# PROC051D_XDS110_Interface_1B.net
KiCad netlist of a schematic drawn in Altium Designer
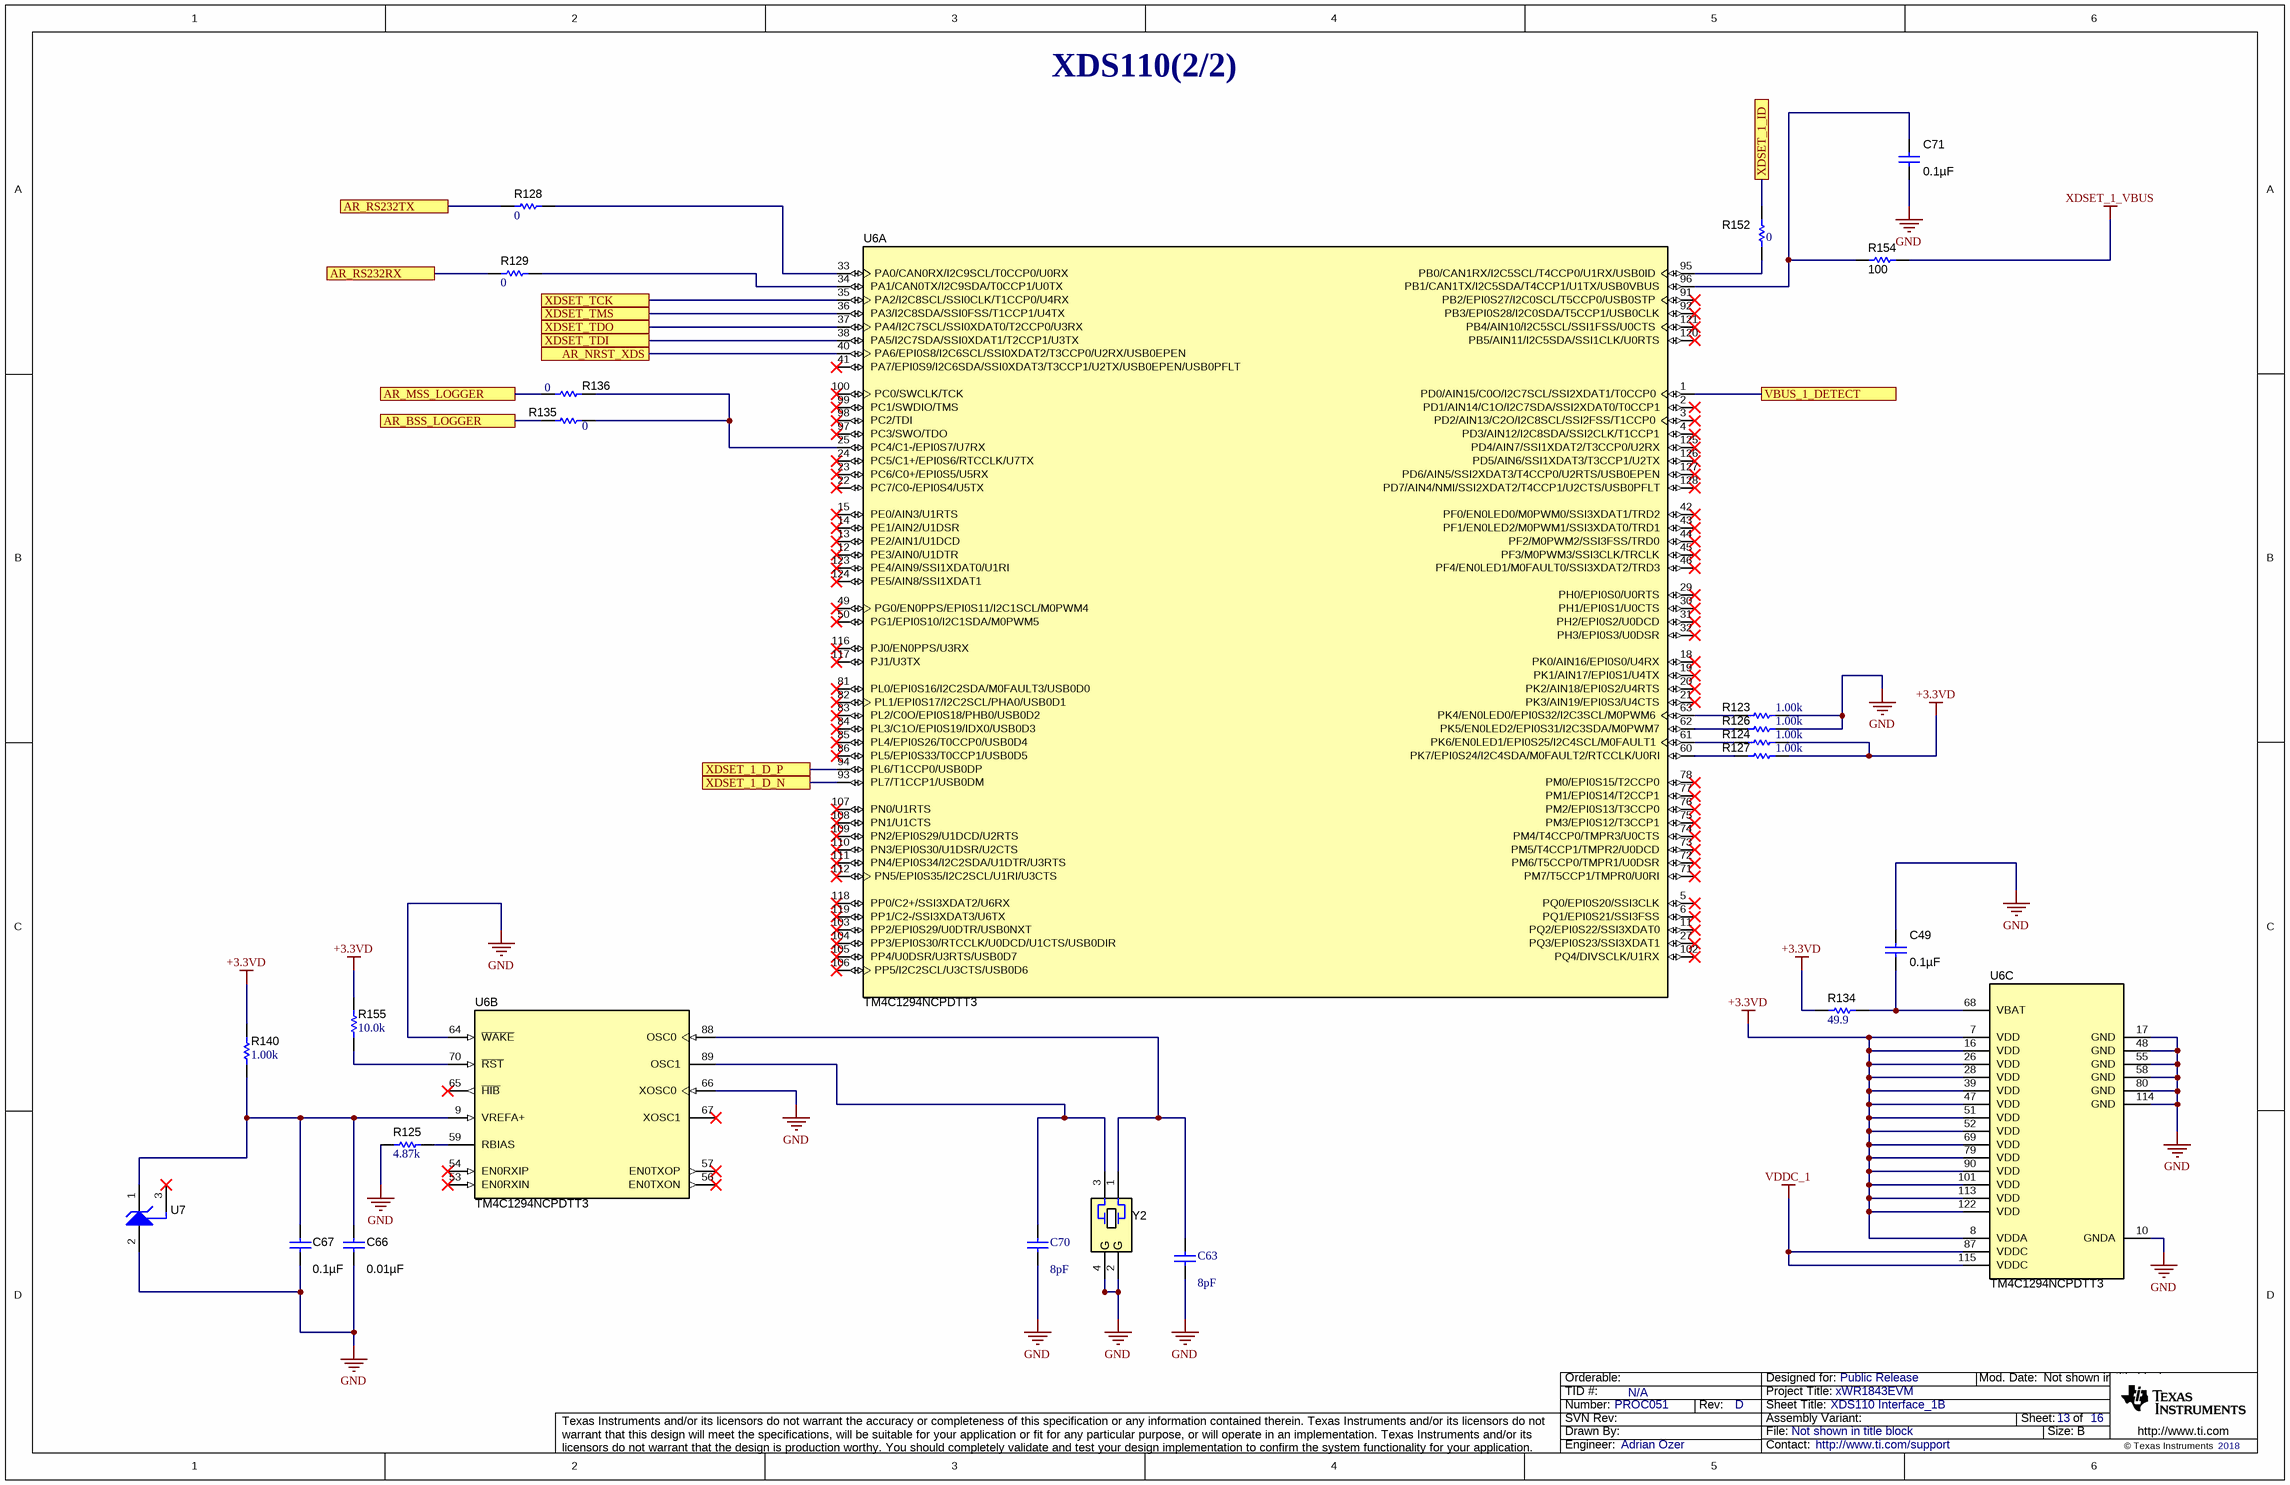
[diagram p0: PROC051D_XDS110 Interface_1B.SchDoc]

(export (version "E")
  (design (tool "Eeschema 10.0.6"))
  (components
    (comp (ref "C49")
      (value "C0402C104K8RACTU")
      (footprint "0402L")
      (description "CAP, CERM, 0.1 µF, 10 V,+/- 10%, X7R, 0402")
      (fields (field (name "MANUFACTURER") "Kemet") (field (name "VALUEDISPLAYED") "0.1µF"))
      (libsource (lib "Altium Vault - TI") (part "CMP-0078241-1"))
    )
    (comp (ref "C63")
      (value "GCM1555C1H8R0DA16D")
      (footprint "0402L")
      (description "Cap Ceramic 8pF 50V C0G 0.5pF SMD 0402 125C Paper T/R")
      (fields (field (name "CAP_F") "8pF") (field (name "MANUFACTURER") "Murata Electronics North America"))
      (libsource (lib "Altium Vault - TI") (part "CMP-0087060-3"))
    )
    (comp (ref "C66")
      (value "C0402C103K4RACTU")
      (footprint "0402L")
      (description "CAP, CERM, 0.01 µF, 16 V,+/- 10%, X7R, 0402")
      (fields (field (name "MANUFACTURER") "Kemet") (field (name "VALUEDISPLAYED") "0.01µF"))
      (libsource (lib "Altium Vault - TI") (part "Capacitor"))
    )
    (comp (ref "C67")
      (value "C0402C104K8RACTU")
      (footprint "0402L")
      (description "CAP, CERM, 0.1 µF, 10 V,+/- 10%, X7R, 0402")
      (fields (field (name "MANUFACTURER") "Kemet") (field (name "VALUEDISPLAYED") "0.1µF"))
      (libsource (lib "Altium Vault - TI") (part "Capacitor"))
    )
    (comp (ref "C70")
      (value "GCM1555C1H8R0DA16D")
      (footprint "0402L")
      (description "Cap Ceramic 8pF 50V C0G 0.5pF SMD 0402 125C Paper T/R")
      (fields (field (name "CAP_F") "8pF") (field (name "MANUFACTURER") "Murata Electronics North America"))
      (libsource (lib "Altium Vault - TI") (part "CMP-0087060-3"))
    )
    (comp (ref "C71")
      (value "C0402C104K8RACTU")
      (footprint "0402L")
      (description "CAP, CERM, 0.1 µF, 10 V,+/- 10%, X7R, 0402")
      (fields (field (name "MANUFACTURER") "Kemet") (field (name "VALUEDISPLAYED") "0.1µF"))
      (libsource (lib "Altium Vault - TI") (part "Capacitor"))
    )
    (comp (ref "R123")
      (value "CRCW04021K00FKED")
      (footprint "0402L")
      (description "RES, 1.00 k, 1%, 0.063 W, AEC-Q200 Grade 0, 0402")
      (fields (field (name "MANUFACTURER") "Vishay-Dale") (field (name "VALUEDISPLAYED") "1.00k"))
      (libsource (lib "Altium Vault - TI") (part "Resistor"))
    )
    (comp (ref "R124")
      (value "CRCW04021K00FKED")
      (footprint "0402L")
      (description "RES, 1.00 k, 1%, 0.063 W, AEC-Q200 Grade 0, 0402")
      (fields (field (name "MANUFACTURER") "Vishay-Dale") (field (name "VALUEDISPLAYED") "1.00k"))
      (libsource (lib "Altium Vault - TI") (part "Resistor"))
    )
    (comp (ref "R125")
      (value "CRCW04024K87FKED")
      (footprint "0402L")
      (description "RES, 4.87 k, 1%, 0.063 W, AEC-Q200 Grade 0, 0402")
      (fields (field (name "MANUFACTURER") "Vishay-Dale") (field (name "VALUEDISPLAYED") "4.87k"))
      (libsource (lib "Altium Vault - TI") (part "Resistor"))
    )
    (comp (ref "R126")
      (value "CRCW04021K00FKED")
      (footprint "0402L")
      (description "RES, 1.00 k, 1%, 0.063 W, AEC-Q200 Grade 0, 0402")
      (fields (field (name "MANUFACTURER") "Vishay-Dale") (field (name "VALUEDISPLAYED") "1.00k"))
      (libsource (lib "Altium Vault - TI") (part "Resistor"))
    )
    (comp (ref "R127")
      (value "CRCW04021K00FKED")
      (footprint "0402L")
      (description "RES, 1.00 k, 1%, 0.063 W, AEC-Q200 Grade 0, 0402")
      (fields (field (name "MANUFACTURER") "Vishay-Dale") (field (name "VALUEDISPLAYED") "1.00k"))
      (libsource (lib "Altium Vault - TI") (part "Resistor"))
    )
    (comp (ref "R128")
      (value "ERJ-2GE0R00X")
      (footprint "0402L")
      (description "RES, 0, 5%, 0.1 W, AEC-Q200 Grade 0, 0402")
      (fields (field (name "MANUFACTURER") "Panasonic") (field (name "VALUEDISPLAYED") "0"))
      (libsource (lib "Altium Vault - TI") (part "Resistor"))
    )
    (comp (ref "R129")
      (value "ERJ-2GE0R00X")
      (footprint "0402L")
      (description "RES, 0, 5%, 0.1 W, AEC-Q200 Grade 0, 0402")
      (fields (field (name "MANUFACTURER") "Panasonic") (field (name "VALUEDISPLAYED") "0"))
      (libsource (lib "Altium Vault - TI") (part "Resistor"))
    )
    (comp (ref "R134")
      (value "CRCW040249R9FKED")
      (footprint "0402L")
      (description "RES, 49.9, 1%, 0.063 W, AEC-Q200 Grade 0, 0402")
      (fields (field (name "MANUFACTURER") "Vishay-Dale") (field (name "VALUEDISPLAYED") "49.9"))
      (libsource (lib "Altium Vault - TI") (part "Resistor"))
    )
    (comp (ref "R135")
      (value "CRCW02010000Z0ED")
      (footprint "0201_Silk")
      (description "RES, 0, 5%, 0.05 W, 0201")
      (fields (field (name "MANUFACTURER") "Vishay-Dale") (field (name "VALUEDISPLAYED") "0"))
      (libsource (lib "Altium Vault - TI") (part "Resistor"))
    )
    (comp (ref "R136")
      (value "CRCW02010000Z0ED")
      (footprint "0201_Silk")
      (description "RES, 0, 5%, 0.05 W, 0201")
      (fields (field (name "MANUFACTURER") "Vishay-Dale") (field (name "VALUEDISPLAYED") "0"))
      (libsource (lib "Altium Vault - TI") (part "Resistor"))
    )
    (comp (ref "R140")
      (value "CRCW04021K00FKED")
      (footprint "0402L")
      (description "RES, 1.00 k, 1%, 0.063 W, AEC-Q200 Grade 0, 0402")
      (fields (field (name "MANUFACTURER") "Vishay-Dale") (field (name "VALUEDISPLAYED") "1.00k"))
      (libsource (lib "Altium Vault - TI") (part "Resistor"))
    )
    (comp (ref "R152")
      (value "ERJ-2GE0R00X")
      (footprint "0402L")
      (description "RES, 0, 5%, 0.1 W, AEC-Q200 Grade 0, 0402")
      (fields (field (name "MANUFACTURER") "Panasonic") (field (name "VALUEDISPLAYED") "0"))
      (libsource (lib "Altium Vault - TI") (part "Resistor"))
    )
    (comp (ref "R154")
      (value "ERJ-2GEJ101X")
      (footprint "0402L")
      (description "RES, 100, 5%, 0.1 W, AEC-Q200 Grade 0, 0402")
      (fields
        (field (name "MANUFACTURER") "Panasonic")
        (field (name "VALUEDISPLAYED") "100")
        (field (name "PUBLISHER") "Texas Instruments")
      )
      (libsource (lib "Altium Vault - TI") (part "Resistor"))
    )
    (comp (ref "R155")
      (value "CRCW040210K0FKED")
      (footprint "0402L")
      (description "RES, 10.0 k, 1%, 0.063 W, AEC-Q200 Grade 0, 0402")
      (fields (field (name "MANUFACTURER") "Vishay-Dale") (field (name "VALUEDISPLAYED") "10.0k"))
      (libsource (lib "Altium Vault - TI") (part "Resistor"))
    )
    (comp (ref "U6")
      (value "TM4C1294NCPDTT3")
      (footprint "PDT0128A")
      (fields (field (name "PARTNUMBER") "TM4C1294NCPDTT3") (field (name "MANUFACTURER") "Texas Instruments"))
      (libsource (lib "Altium Vault - TI") (part "TI-TM4C1294NCPDT-128"))
    )
    (comp (ref "U7")
      (value "LM4040C25QDBZR")
      (footprint "DBZ0003A_N")
      (fields (field (name "MANUFACTURER") "Texas Instruments"))
      (libsource (lib "Altium Vault - TI") (part "TI-LM4040C25DBZ3"))
    )
    (comp (ref "Y2")
      (value "NX3225SA-16.000M-STD-CRS-2")
      (footprint "NDK_NX3225SA")
      (description "Crystal, 16 MHz, 15 ppm, 8 pF, AEC-Q200 Grade 1, SMD")
      (fields (field (name "MANUFACTURER") "NDK"))
      (libsource (lib "Altium Vault - TI") (part "CMP-0078214-2"))
    )
  )
  (nets
    (net (code "1") (name "+3.3VD") (class "Default")
      (node (ref "R124") (pin "2") (pinfunction "2_2") (pintype "passive"))
      (node (ref "R127") (pin "2") (pinfunction "2_2") (pintype "passive"))
      (node (ref "R134") (pin "2") (pinfunction "2_2") (pintype "passive"))
      (node (ref "R140") (pin "2") (pinfunction "2_2") (pintype "passive"))
      (node (ref "R155") (pin "2") (pinfunction "2_2") (pintype "passive"))
      (node (ref "U6") (pin "101") (pinfunction "VDD_101") (pintype "power_in"))
      (node (ref "U6") (pin "113") (pinfunction "VDD_113") (pintype "power_in"))
      (node (ref "U6") (pin "122") (pinfunction "VDD_122") (pintype "power_in"))
      (node (ref "U6") (pin "16") (pinfunction "VDD_16") (pintype "power_in"))
      (node (ref "U6") (pin "26") (pinfunction "VDD_26") (pintype "power_in"))
      (node (ref "U6") (pin "28") (pinfunction "VDD_28") (pintype "power_in"))
      (node (ref "U6") (pin "39") (pinfunction "VDD_39") (pintype "power_in"))
      (node (ref "U6") (pin "47") (pinfunction "VDD_47") (pintype "power_in"))
      (node (ref "U6") (pin "51") (pinfunction "VDD_51") (pintype "power_in"))
      (node (ref "U6") (pin "52") (pinfunction "VDD_52") (pintype "power_in"))
      (node (ref "U6") (pin "69") (pinfunction "VDD_69") (pintype "power_in"))
      (node (ref "U6") (pin "7") (pinfunction "VDD_7") (pintype "power_in"))
      (node (ref "U6") (pin "79") (pinfunction "VDD_79") (pintype "power_in"))
      (node (ref "U6") (pin "8") (pinfunction "VDDA_8") (pintype "power_in"))
      (node (ref "U6") (pin "90") (pinfunction "VDD_90") (pintype "power_in"))
    )
    (net (code "2") (name "/AR_BSS_LOGGER") (class "Default")
      (node (ref "R135") (pin "1") (pinfunction "1_1") (pintype "passive"))
    )
    (net (code "3") (name "/AR_MSS_LOGGER") (class "Default")
      (node (ref "R136") (pin "1") (pinfunction "1_1") (pintype "passive"))
    )
    (net (code "4") (name "/AR_NRST_XDS") (class "Default")
      (node (ref "U6") (pin "40") (pinfunction "PA6/EPI0S8/I2C6SCL/SSI0XDAT2/T3CCP0/U2RX/USB0EPEN_40") (pintype "bidirectional"))
    )
    (net (code "5") (name "/AR_RS232RX") (class "Default")
      (node (ref "R129") (pin "1") (pinfunction "1_1") (pintype "passive"))
    )
    (net (code "6") (name "/AR_RS232TX") (class "Default")
      (node (ref "R128") (pin "1") (pinfunction "1_1") (pintype "passive"))
    )
    (net (code "7") (name "/VBUS_1_DETECT") (class "Default")
      (node (ref "U6") (pin "1") (pinfunction "PD0/AIN15/C0O/I2C7SCL/SSI2XDAT1/T0CCP0_1") (pintype "bidirectional"))
    )
    (net (code "8") (name "/XDSET_1_D_N") (class "Default")
      (node (ref "U6") (pin "93") (pinfunction "PL7/T1CCP1/USB0DM_93") (pintype "bidirectional"))
    )
    (net (code "9") (name "/XDSET_1_D_P") (class "Default")
      (node (ref "U6") (pin "94") (pinfunction "PL6/T1CCP0/USB0DP_94") (pintype "bidirectional"))
    )
    (net (code "10") (name "/XDSET_1_ID") (class "Default")
      (node (ref "R152") (pin "2") (pinfunction "2_2") (pintype "passive"))
    )
    (net (code "11") (name "/XDSET_TCK") (class "Default")
      (node (ref "U6") (pin "35") (pinfunction "PA2/I2C8SCL/SSI0CLK/T1CCP0/U4RX_35") (pintype "bidirectional"))
    )
    (net (code "12") (name "/XDSET_TDI") (class "Default")
      (node (ref "U6") (pin "38") (pinfunction "PA5/I2C7SDA/SSI0XDAT1/T2CCP1/U3TX_38") (pintype "bidirectional"))
    )
    (net (code "13") (name "/XDSET_TDO") (class "Default")
      (node (ref "U6") (pin "37") (pinfunction "PA4/I2C7SCL/SSI0XDAT0/T2CCP0/U3RX_37") (pintype "bidirectional"))
    )
    (net (code "14") (name "/XDSET_TMS") (class "Default")
      (node (ref "U6") (pin "36") (pinfunction "PA3/I2C8SDA/SSI0FSS/T1CCP1/U4TX_36") (pintype "bidirectional"))
    )
    (net (code "15") (name "GND") (class "Default")
      (node (ref "C49") (pin "1") (pinfunction "1_1") (pintype "passive"))
      (node (ref "C63") (pin "2") (pinfunction "2_2") (pintype "passive"))
      (node (ref "C66") (pin "1") (pinfunction "1_1") (pintype "passive"))
      (node (ref "C67") (pin "1") (pinfunction "1_1") (pintype "passive"))
      (node (ref "C70") (pin "2") (pinfunction "2_2") (pintype "passive"))
      (node (ref "C71") (pin "1") (pinfunction "1_1") (pintype "passive"))
      (node (ref "R123") (pin "2") (pinfunction "2_2") (pintype "passive"))
      (node (ref "R125") (pin "1") (pinfunction "1_1") (pintype "passive"))
      (node (ref "R126") (pin "2") (pinfunction "2_2") (pintype "passive"))
      (node (ref "U6") (pin "10") (pinfunction "GNDA_10") (pintype "power_in"))
      (node (ref "U6") (pin "114") (pinfunction "GND_114") (pintype "power_in"))
      (node (ref "U6") (pin "17") (pinfunction "GND_17") (pintype "power_in"))
      (node (ref "U6") (pin "48") (pinfunction "GND_48") (pintype "power_in"))
      (node (ref "U6") (pin "55") (pinfunction "GND_55") (pintype "power_in"))
      (node (ref "U6") (pin "58") (pinfunction "GND_58") (pintype "power_in"))
      (node (ref "U6") (pin "64") (pinfunction "~{WAKE}_64") (pintype "input"))
      (node (ref "U6") (pin "66") (pinfunction "XOSC0_66") (pintype "input"))
      (node (ref "U6") (pin "80") (pinfunction "GND_80") (pintype "power_in"))
      (node (ref "U7") (pin "2") (pinfunction "ANODE_2") (pintype "passive"))
      (node (ref "Y2") (pin "2") (pinfunction "GND_2") (pintype "power_in"))
      (node (ref "Y2") (pin "4") (pinfunction "GND_4") (pintype "power_in"))
    )
    (net (code "16") (name "Net-(U6A-PA0{slash}CAN0RX{slash}I2C9SCL{slash}T0CCP0{slash}U0RX)") (class "Default")
      (node (ref "R128") (pin "2") (pinfunction "2_2") (pintype "passive"))
      (node (ref "U6") (pin "33") (pinfunction "PA0/CAN0RX/I2C9SCL/T0CCP0/U0RX_33") (pintype "bidirectional"))
    )
    (net (code "17") (name "Net-(U6A-PA1{slash}CAN0TX{slash}I2C9SDA{slash}T0CCP1{slash}U0TX)") (class "Default")
      (node (ref "R129") (pin "2") (pinfunction "2_2") (pintype "passive"))
      (node (ref "U6") (pin "34") (pinfunction "PA1/CAN0TX/I2C9SDA/T0CCP1/U0TX_34") (pintype "bidirectional"))
    )
    (net (code "18") (name "Net-(U6A-PB0{slash}CAN1RX{slash}I2C5SCL{slash}T4CCP0{slash}U1RX{slash}USB0ID)") (class "Default")
      (node (ref "R152") (pin "1") (pinfunction "1_1") (pintype "passive"))
      (node (ref "U6") (pin "95") (pinfunction "PB0/CAN1RX/I2C5SCL/T4CCP0/U1RX/USB0ID_95") (pintype "bidirectional"))
    )
    (net (code "19") (name "Net-(U6A-PB1{slash}CAN1TX{slash}I2C5SDA{slash}T4CCP1{slash}U1TX{slash}USB0VBUS)") (class "Default")
      (node (ref "C71") (pin "2") (pinfunction "2_2") (pintype "passive"))
      (node (ref "R154") (pin "1") (pinfunction "1_1") (pintype "passive"))
      (node (ref "U6") (pin "96") (pinfunction "PB1/CAN1TX/I2C5SDA/T4CCP1/U1TX/USB0VBUS_96") (pintype "bidirectional"))
    )
    (net (code "20") (name "Net-(U6A-PC4{slash}C1-{slash}EPI0S7{slash}U7RX)") (class "Default")
      (node (ref "R135") (pin "2") (pinfunction "2_2") (pintype "passive"))
      (node (ref "R136") (pin "2") (pinfunction "2_2") (pintype "passive"))
      (node (ref "U6") (pin "25") (pinfunction "PC4/C1-/EPI0S7/U7RX_25") (pintype "bidirectional"))
    )
    (net (code "21") (name "Net-(U6A-PK4{slash}EN0LED0{slash}EPI0S32{slash}I2C3SCL{slash}M0PWM6)") (class "Default")
      (node (ref "R123") (pin "1") (pinfunction "1_1") (pintype "passive"))
      (node (ref "U6") (pin "63") (pinfunction "PK4/EN0LED0/EPI0S32/I2C3SCL/M0PWM6_63") (pintype "bidirectional"))
    )
    (net (code "22") (name "Net-(U6A-PK5{slash}EN0LED2{slash}EPI0S31{slash}I2C3SDA{slash}M0PWM7)") (class "Default")
      (node (ref "R126") (pin "1") (pinfunction "1_1") (pintype "passive"))
      (node (ref "U6") (pin "62") (pinfunction "PK5/EN0LED2/EPI0S31/I2C3SDA/M0PWM7_62") (pintype "bidirectional"))
    )
    (net (code "23") (name "Net-(U6A-PK6{slash}EN0LED1{slash}EPI0S25{slash}I2C4SCL{slash}M0FAULT1)") (class "Default")
      (node (ref "R124") (pin "1") (pinfunction "1_1") (pintype "passive"))
      (node (ref "U6") (pin "61") (pinfunction "PK6/EN0LED1/EPI0S25/I2C4SCL/M0FAULT1_61") (pintype "bidirectional"))
    )
    (net (code "24") (name "Net-(U6A-PK7{slash}EPI0S24{slash}I2C4SDA{slash}M0FAULT2{slash}RTCCLK{slash}U0RI)") (class "Default")
      (node (ref "R127") (pin "1") (pinfunction "1_1") (pintype "passive"))
      (node (ref "U6") (pin "60") (pinfunction "PK7/EPI0S24/I2C4SDA/M0FAULT2/RTCCLK/U0RI_60") (pintype "bidirectional"))
    )
    (net (code "25") (name "Net-(U6B-OSC0)") (class "Default")
      (node (ref "C63") (pin "1") (pinfunction "1_1") (pintype "passive"))
      (node (ref "U6") (pin "88") (pinfunction "OSC0_88") (pintype "input"))
      (node (ref "Y2") (pin "1") (pinfunction "1_1") (pintype "passive"))
    )
    (net (code "26") (name "Net-(U6B-OSC1)") (class "Default")
      (node (ref "C70") (pin "1") (pinfunction "1_1") (pintype "passive"))
      (node (ref "U6") (pin "89") (pinfunction "OSC1_89") (pintype "passive"))
      (node (ref "Y2") (pin "3") (pinfunction "3_3") (pintype "passive"))
    )
    (net (code "27") (name "Net-(U6B-RBIAS)") (class "Default")
      (node (ref "R125") (pin "2") (pinfunction "2_2") (pintype "passive"))
      (node (ref "U6") (pin "59") (pinfunction "RBIAS_59") (pintype "passive"))
    )
    (net (code "28") (name "Net-(U6B-VREFA+)") (class "Default")
      (node (ref "C66") (pin "2") (pinfunction "2_2") (pintype "passive"))
      (node (ref "C67") (pin "2") (pinfunction "2_2") (pintype "passive"))
      (node (ref "R140") (pin "1") (pinfunction "1_1") (pintype "passive"))
      (node (ref "U6") (pin "9") (pinfunction "VREFA+_9") (pintype "input"))
      (node (ref "U7") (pin "1") (pinfunction "CATHODE_1") (pintype "passive"))
    )
    (net (code "29") (name "Net-(U6B-~{RST})") (class "Default")
      (node (ref "R155") (pin "1") (pinfunction "1_1") (pintype "passive"))
      (node (ref "U6") (pin "70") (pinfunction "~{RST}_70") (pintype "input"))
    )
    (net (code "30") (name "Net-(U6C-VBAT)") (class "Default")
      (node (ref "C49") (pin "2") (pinfunction "2_2") (pintype "passive"))
      (node (ref "R134") (pin "1") (pinfunction "1_1") (pintype "passive"))
      (node (ref "U6") (pin "68") (pinfunction "VBAT_68") (pintype "power_in"))
    )
    (net (code "31") (name "VDDC_1") (class "Default")
      (node (ref "U6") (pin "115") (pinfunction "VDDC_115") (pintype "power_in"))
      (node (ref "U6") (pin "87") (pinfunction "VDDC_87") (pintype "power_in"))
    )
    (net (code "32") (name "XDSET_1_VBUS") (class "Default")
      (node (ref "R154") (pin "2") (pinfunction "2_2") (pintype "passive"))
    )
    (net (code "33") (name "unconnected-(U6A-PA7{slash}EPI0S9{slash}I2C6SDA{slash}SSI0XDAT3{slash}T3CCP1{slash}U2TX{slash}USB0EPEN{slash}USB0PFLT-Pad41)") (class "Default")
      (node (ref "U6") (pin "41") (pinfunction "PA7/EPI0S9/I2C6SDA/SSI0XDAT3/T3CCP1/U2TX/USB0EPEN/USB0PFLT_41") (pintype "bidirectional+no_connect"))
    )
    (net (code "34") (name "unconnected-(U6A-PB2{slash}EPI0S27{slash}I2C0SCL{slash}T5CCP0{slash}USB0STP-Pad91)") (class "Default")
      (node (ref "U6") (pin "91") (pinfunction "PB2/EPI0S27/I2C0SCL/T5CCP0/USB0STP_91") (pintype "bidirectional+no_connect"))
    )
    (net (code "35") (name "unconnected-(U6A-PB3{slash}EPI0S28{slash}I2C0SDA{slash}T5CCP1{slash}USB0CLK-Pad92)") (class "Default")
      (node (ref "U6") (pin "92") (pinfunction "PB3/EPI0S28/I2C0SDA/T5CCP1/USB0CLK_92") (pintype "bidirectional+no_connect"))
    )
    (net (code "36") (name "unconnected-(U6A-PB4{slash}AIN10{slash}I2C5SCL{slash}SSI1FSS{slash}U0CTS-Pad121)") (class "Default")
      (node (ref "U6") (pin "121") (pinfunction "PB4/AIN10/I2C5SCL/SSI1FSS/U0CTS_121") (pintype "bidirectional+no_connect"))
    )
    (net (code "37") (name "unconnected-(U6A-PB5{slash}AIN11{slash}I2C5SDA{slash}SSI1CLK{slash}U0RTS-Pad120)") (class "Default")
      (node (ref "U6") (pin "120") (pinfunction "PB5/AIN11/I2C5SDA/SSI1CLK/U0RTS_120") (pintype "bidirectional+no_connect"))
    )
    (net (code "38") (name "unconnected-(U6A-PC0{slash}SWCLK{slash}TCK-Pad100)") (class "Default")
      (node (ref "U6") (pin "100") (pinfunction "PC0/SWCLK/TCK_100") (pintype "bidirectional+no_connect"))
    )
    (net (code "39") (name "unconnected-(U6A-PC1{slash}SWDIO{slash}TMS-Pad99)") (class "Default")
      (node (ref "U6") (pin "99") (pinfunction "PC1/SWDIO/TMS_99") (pintype "bidirectional+no_connect"))
    )
    (net (code "40") (name "unconnected-(U6A-PC2{slash}TDI-Pad98)") (class "Default")
      (node (ref "U6") (pin "98") (pinfunction "PC2/TDI_98") (pintype "bidirectional+no_connect"))
    )
    (net (code "41") (name "unconnected-(U6A-PC3{slash}SWO{slash}TDO-Pad97)") (class "Default")
      (node (ref "U6") (pin "97") (pinfunction "PC3/SWO/TDO_97") (pintype "bidirectional+no_connect"))
    )
    (net (code "42") (name "unconnected-(U6A-PC5{slash}C1+{slash}EPI0S6{slash}RTCCLK{slash}U7TX-Pad24)") (class "Default")
      (node (ref "U6") (pin "24") (pinfunction "PC5/C1+/EPI0S6/RTCCLK/U7TX_24") (pintype "bidirectional+no_connect"))
    )
    (net (code "43") (name "unconnected-(U6A-PC6{slash}C0+{slash}EPI0S5{slash}U5RX-Pad23)") (class "Default")
      (node (ref "U6") (pin "23") (pinfunction "PC6/C0+/EPI0S5/U5RX_23") (pintype "bidirectional+no_connect"))
    )
    (net (code "44") (name "unconnected-(U6A-PC7{slash}C0-{slash}EPI0S4{slash}U5TX-Pad22)") (class "Default")
      (node (ref "U6") (pin "22") (pinfunction "PC7/C0-/EPI0S4/U5TX_22") (pintype "bidirectional+no_connect"))
    )
    (net (code "45") (name "unconnected-(U6A-PD1{slash}AIN14{slash}C1O{slash}I2C7SDA{slash}SSI2XDAT0{slash}T0CCP1-Pad2)") (class "Default")
      (node (ref "U6") (pin "2") (pinfunction "PD1/AIN14/C1O/I2C7SDA/SSI2XDAT0/T0CCP1_2") (pintype "bidirectional+no_connect"))
    )
    (net (code "46") (name "unconnected-(U6A-PD2{slash}AIN13{slash}C2O{slash}I2C8SCL{slash}SSI2FSS{slash}T1CCP0-Pad3)") (class "Default")
      (node (ref "U6") (pin "3") (pinfunction "PD2/AIN13/C2O/I2C8SCL/SSI2FSS/T1CCP0_3") (pintype "bidirectional+no_connect"))
    )
    (net (code "47") (name "unconnected-(U6A-PD3{slash}AIN12{slash}I2C8SDA{slash}SSI2CLK{slash}T1CCP1-Pad4)") (class "Default")
      (node (ref "U6") (pin "4") (pinfunction "PD3/AIN12/I2C8SDA/SSI2CLK/T1CCP1_4") (pintype "bidirectional+no_connect"))
    )
    (net (code "48") (name "unconnected-(U6A-PD4{slash}AIN7{slash}SSI1XDAT2{slash}T3CCP0{slash}U2RX-Pad125)") (class "Default")
      (node (ref "U6") (pin "125") (pinfunction "PD4/AIN7/SSI1XDAT2/T3CCP0/U2RX_125") (pintype "bidirectional+no_connect"))
    )
    (net (code "49") (name "unconnected-(U6A-PD5{slash}AIN6{slash}SSI1XDAT3{slash}T3CCP1{slash}U2TX-Pad126)") (class "Default")
      (node (ref "U6") (pin "126") (pinfunction "PD5/AIN6/SSI1XDAT3/T3CCP1/U2TX_126") (pintype "bidirectional+no_connect"))
    )
    (net (code "50") (name "unconnected-(U6A-PD6{slash}AIN5{slash}SSI2XDAT3{slash}T4CCP0{slash}U2RTS{slash}USB0EPEN-Pad127)") (class "Default")
      (node (ref "U6") (pin "127") (pinfunction "PD6/AIN5/SSI2XDAT3/T4CCP0/U2RTS/USB0EPEN_127") (pintype "bidirectional+no_connect"))
    )
    (net (code "51") (name "unconnected-(U6A-PD7{slash}AIN4{slash}NMI{slash}SSI2XDAT2{slash}T4CCP1{slash}U2CTS{slash}USB0PFLT-Pad128)") (class "Default")
      (node (ref "U6") (pin "128") (pinfunction "PD7/AIN4/NMI/SSI2XDAT2/T4CCP1/U2CTS/USB0PFLT_128") (pintype "bidirectional+no_connect"))
    )
    (net (code "52") (name "unconnected-(U6A-PE0{slash}AIN3{slash}U1RTS-Pad15)") (class "Default")
      (node (ref "U6") (pin "15") (pinfunction "PE0/AIN3/U1RTS_15") (pintype "bidirectional+no_connect"))
    )
    (net (code "53") (name "unconnected-(U6A-PE1{slash}AIN2{slash}U1DSR-Pad14)") (class "Default")
      (node (ref "U6") (pin "14") (pinfunction "PE1/AIN2/U1DSR_14") (pintype "bidirectional+no_connect"))
    )
    (net (code "54") (name "unconnected-(U6A-PE2{slash}AIN1{slash}U1DCD-Pad13)") (class "Default")
      (node (ref "U6") (pin "13") (pinfunction "PE2/AIN1/U1DCD_13") (pintype "bidirectional+no_connect"))
    )
    (net (code "55") (name "unconnected-(U6A-PE3{slash}AIN0{slash}U1DTR-Pad12)") (class "Default")
      (node (ref "U6") (pin "12") (pinfunction "PE3/AIN0/U1DTR_12") (pintype "bidirectional+no_connect"))
    )
    (net (code "56") (name "unconnected-(U6A-PE4{slash}AIN9{slash}SSI1XDAT0{slash}U1RI-Pad123)") (class "Default")
      (node (ref "U6") (pin "123") (pinfunction "PE4/AIN9/SSI1XDAT0/U1RI_123") (pintype "bidirectional+no_connect"))
    )
    (net (code "57") (name "unconnected-(U6A-PE5{slash}AIN8{slash}SSI1XDAT1-Pad124)") (class "Default")
      (node (ref "U6") (pin "124") (pinfunction "PE5/AIN8/SSI1XDAT1_124") (pintype "bidirectional+no_connect"))
    )
    (net (code "58") (name "unconnected-(U6A-PF0{slash}EN0LED0{slash}M0PWM0{slash}SSI3XDAT1{slash}TRD2-Pad42)") (class "Default")
      (node (ref "U6") (pin "42") (pinfunction "PF0/EN0LED0/M0PWM0/SSI3XDAT1/TRD2_42") (pintype "bidirectional+no_connect"))
    )
    (net (code "59") (name "unconnected-(U6A-PF1{slash}EN0LED2{slash}M0PWM1{slash}SSI3XDAT0{slash}TRD1-Pad43)") (class "Default")
      (node (ref "U6") (pin "43") (pinfunction "PF1/EN0LED2/M0PWM1/SSI3XDAT0/TRD1_43") (pintype "bidirectional+no_connect"))
    )
    (net (code "60") (name "unconnected-(U6A-PF2{slash}M0PWM2{slash}SSI3FSS{slash}TRD0-Pad44)") (class "Default")
      (node (ref "U6") (pin "44") (pinfunction "PF2/M0PWM2/SSI3FSS/TRD0_44") (pintype "bidirectional+no_connect"))
    )
    (net (code "61") (name "unconnected-(U6A-PF3{slash}M0PWM3{slash}SSI3CLK{slash}TRCLK-Pad45)") (class "Default")
      (node (ref "U6") (pin "45") (pinfunction "PF3/M0PWM3/SSI3CLK/TRCLK_45") (pintype "bidirectional+no_connect"))
    )
    (net (code "62") (name "unconnected-(U6A-PF4{slash}EN0LED1{slash}M0FAULT0{slash}SSI3XDAT2{slash}TRD3-Pad46)") (class "Default")
      (node (ref "U6") (pin "46") (pinfunction "PF4/EN0LED1/M0FAULT0/SSI3XDAT2/TRD3_46") (pintype "bidirectional+no_connect"))
    )
    (net (code "63") (name "unconnected-(U6A-PG0{slash}EN0PPS{slash}EPI0S11{slash}I2C1SCL{slash}M0PWM4-Pad49)") (class "Default")
      (node (ref "U6") (pin "49") (pinfunction "PG0/EN0PPS/EPI0S11/I2C1SCL/M0PWM4_49") (pintype "bidirectional+no_connect"))
    )
    (net (code "64") (name "unconnected-(U6A-PG1{slash}EPI0S10{slash}I2C1SDA{slash}M0PWM5-Pad50)") (class "Default")
      (node (ref "U6") (pin "50") (pinfunction "PG1/EPI0S10/I2C1SDA/M0PWM5_50") (pintype "bidirectional+no_connect"))
    )
    (net (code "65") (name "unconnected-(U6A-PH0{slash}EPI0S0{slash}U0RTS-Pad29)") (class "Default")
      (node (ref "U6") (pin "29") (pinfunction "PH0/EPI0S0/U0RTS_29") (pintype "bidirectional+no_connect"))
    )
    (net (code "66") (name "unconnected-(U6A-PH1{slash}EPI0S1{slash}U0CTS-Pad30)") (class "Default")
      (node (ref "U6") (pin "30") (pinfunction "PH1/EPI0S1/U0CTS_30") (pintype "bidirectional+no_connect"))
    )
    (net (code "67") (name "unconnected-(U6A-PH2{slash}EPI0S2{slash}U0DCD-Pad31)") (class "Default")
      (node (ref "U6") (pin "31") (pinfunction "PH2/EPI0S2/U0DCD_31") (pintype "bidirectional+no_connect"))
    )
    (net (code "68") (name "unconnected-(U6A-PH3{slash}EPI0S3{slash}U0DSR-Pad32)") (class "Default")
      (node (ref "U6") (pin "32") (pinfunction "PH3/EPI0S3/U0DSR_32") (pintype "bidirectional+no_connect"))
    )
    (net (code "69") (name "unconnected-(U6A-PJ0{slash}EN0PPS{slash}U3RX-Pad116)") (class "Default")
      (node (ref "U6") (pin "116") (pinfunction "PJ0/EN0PPS/U3RX_116") (pintype "bidirectional+no_connect"))
    )
    (net (code "70") (name "unconnected-(U6A-PJ1{slash}U3TX-Pad117)") (class "Default")
      (node (ref "U6") (pin "117") (pinfunction "PJ1/U3TX_117") (pintype "bidirectional+no_connect"))
    )
    (net (code "71") (name "unconnected-(U6A-PK0{slash}AIN16{slash}EPI0S0{slash}U4RX-Pad18)") (class "Default")
      (node (ref "U6") (pin "18") (pinfunction "PK0/AIN16/EPI0S0/U4RX_18") (pintype "bidirectional+no_connect"))
    )
    (net (code "72") (name "unconnected-(U6A-PK1{slash}AIN17{slash}EPI0S1{slash}U4TX-Pad19)") (class "Default")
      (node (ref "U6") (pin "19") (pinfunction "PK1/AIN17/EPI0S1/U4TX_19") (pintype "bidirectional+no_connect"))
    )
    (net (code "73") (name "unconnected-(U6A-PK2{slash}AIN18{slash}EPI0S2{slash}U4RTS-Pad20)") (class "Default")
      (node (ref "U6") (pin "20") (pinfunction "PK2/AIN18/EPI0S2/U4RTS_20") (pintype "bidirectional+no_connect"))
    )
    (net (code "74") (name "unconnected-(U6A-PK3{slash}AIN19{slash}EPI0S3{slash}U4CTS-Pad21)") (class "Default")
      (node (ref "U6") (pin "21") (pinfunction "PK3/AIN19/EPI0S3/U4CTS_21") (pintype "bidirectional+no_connect"))
    )
    (net (code "75") (name "unconnected-(U6A-PL0{slash}EPI0S16{slash}I2C2SDA{slash}M0FAULT3{slash}USB0D0-Pad81)") (class "Default")
      (node (ref "U6") (pin "81") (pinfunction "PL0/EPI0S16/I2C2SDA/M0FAULT3/USB0D0_81") (pintype "bidirectional+no_connect"))
    )
    (net (code "76") (name "unconnected-(U6A-PL1{slash}EPI0S17{slash}I2C2SCL{slash}PHA0{slash}USB0D1-Pad82)") (class "Default")
      (node (ref "U6") (pin "82") (pinfunction "PL1/EPI0S17/I2C2SCL/PHA0/USB0D1_82") (pintype "bidirectional+no_connect"))
    )
    (net (code "77") (name "unconnected-(U6A-PL2{slash}C0O{slash}EPI0S18{slash}PHB0{slash}USB0D2-Pad83)") (class "Default")
      (node (ref "U6") (pin "83") (pinfunction "PL2/C0O/EPI0S18/PHB0/USB0D2_83") (pintype "bidirectional+no_connect"))
    )
    (net (code "78") (name "unconnected-(U6A-PL3{slash}C1O{slash}EPI0S19{slash}IDX0{slash}USB0D3-Pad84)") (class "Default")
      (node (ref "U6") (pin "84") (pinfunction "PL3/C1O/EPI0S19/IDX0/USB0D3_84") (pintype "bidirectional+no_connect"))
    )
    (net (code "79") (name "unconnected-(U6A-PL4{slash}EPI0S26{slash}T0CCP0{slash}USB0D4-Pad85)") (class "Default")
      (node (ref "U6") (pin "85") (pinfunction "PL4/EPI0S26/T0CCP0/USB0D4_85") (pintype "bidirectional+no_connect"))
    )
    (net (code "80") (name "unconnected-(U6A-PL5{slash}EPI0S33{slash}T0CCP1{slash}USB0D5-Pad86)") (class "Default")
      (node (ref "U6") (pin "86") (pinfunction "PL5/EPI0S33/T0CCP1/USB0D5_86") (pintype "bidirectional+no_connect"))
    )
    (net (code "81") (name "unconnected-(U6A-PM0{slash}EPI0S15{slash}T2CCP0-Pad78)") (class "Default")
      (node (ref "U6") (pin "78") (pinfunction "PM0/EPI0S15/T2CCP0_78") (pintype "bidirectional+no_connect"))
    )
    (net (code "82") (name "unconnected-(U6A-PM1{slash}EPI0S14{slash}T2CCP1-Pad77)") (class "Default")
      (node (ref "U6") (pin "77") (pinfunction "PM1/EPI0S14/T2CCP1_77") (pintype "bidirectional+no_connect"))
    )
    (net (code "83") (name "unconnected-(U6A-PM2{slash}EPI0S13{slash}T3CCP0-Pad76)") (class "Default")
      (node (ref "U6") (pin "76") (pinfunction "PM2/EPI0S13/T3CCP0_76") (pintype "bidirectional+no_connect"))
    )
    (net (code "84") (name "unconnected-(U6A-PM3{slash}EPI0S12{slash}T3CCP1-Pad75)") (class "Default")
      (node (ref "U6") (pin "75") (pinfunction "PM3/EPI0S12/T3CCP1_75") (pintype "bidirectional+no_connect"))
    )
    (net (code "85") (name "unconnected-(U6A-PM4{slash}T4CCP0{slash}TMPR3{slash}U0CTS-Pad74)") (class "Default")
      (node (ref "U6") (pin "74") (pinfunction "PM4/T4CCP0/TMPR3/U0CTS_74") (pintype "bidirectional+no_connect"))
    )
    (net (code "86") (name "unconnected-(U6A-PM5{slash}T4CCP1{slash}TMPR2{slash}U0DCD-Pad73)") (class "Default")
      (node (ref "U6") (pin "73") (pinfunction "PM5/T4CCP1/TMPR2/U0DCD_73") (pintype "bidirectional+no_connect"))
    )
    (net (code "87") (name "unconnected-(U6A-PM6{slash}T5CCP0{slash}TMPR1{slash}U0DSR-Pad72)") (class "Default")
      (node (ref "U6") (pin "72") (pinfunction "PM6/T5CCP0/TMPR1/U0DSR_72") (pintype "bidirectional+no_connect"))
    )
    (net (code "88") (name "unconnected-(U6A-PM7{slash}T5CCP1{slash}TMPR0{slash}U0RI-Pad71)") (class "Default")
      (node (ref "U6") (pin "71") (pinfunction "PM7/T5CCP1/TMPR0/U0RI_71") (pintype "bidirectional+no_connect"))
    )
    (net (code "89") (name "unconnected-(U6A-PN0{slash}U1RTS-Pad107)") (class "Default")
      (node (ref "U6") (pin "107") (pinfunction "PN0/U1RTS_107") (pintype "bidirectional+no_connect"))
    )
    (net (code "90") (name "unconnected-(U6A-PN1{slash}U1CTS-Pad108)") (class "Default")
      (node (ref "U6") (pin "108") (pinfunction "PN1/U1CTS_108") (pintype "bidirectional+no_connect"))
    )
    (net (code "91") (name "unconnected-(U6A-PN2{slash}EPI0S29{slash}U1DCD{slash}U2RTS-Pad109)") (class "Default")
      (node (ref "U6") (pin "109") (pinfunction "PN2/EPI0S29/U1DCD/U2RTS_109") (pintype "bidirectional+no_connect"))
    )
    (net (code "92") (name "unconnected-(U6A-PN3{slash}EPI0S30{slash}U1DSR{slash}U2CTS-Pad110)") (class "Default")
      (node (ref "U6") (pin "110") (pinfunction "PN3/EPI0S30/U1DSR/U2CTS_110") (pintype "bidirectional+no_connect"))
    )
    (net (code "93") (name "unconnected-(U6A-PN4{slash}EPI0S34{slash}I2C2SDA{slash}U1DTR{slash}U3RTS-Pad111)") (class "Default")
      (node (ref "U6") (pin "111") (pinfunction "PN4/EPI0S34/I2C2SDA/U1DTR/U3RTS_111") (pintype "bidirectional+no_connect"))
    )
    (net (code "94") (name "unconnected-(U6A-PN5{slash}EPI0S35{slash}I2C2SCL{slash}U1RI{slash}U3CTS-Pad112)") (class "Default")
      (node (ref "U6") (pin "112") (pinfunction "PN5/EPI0S35/I2C2SCL/U1RI/U3CTS_112") (pintype "bidirectional+no_connect"))
    )
    (net (code "95") (name "unconnected-(U6A-PP0{slash}C2+{slash}SSI3XDAT2{slash}U6RX-Pad118)") (class "Default")
      (node (ref "U6") (pin "118") (pinfunction "PP0/C2+/SSI3XDAT2/U6RX_118") (pintype "bidirectional+no_connect"))
    )
    (net (code "96") (name "unconnected-(U6A-PP1{slash}C2-{slash}SSI3XDAT3{slash}U6TX-Pad119)") (class "Default")
      (node (ref "U6") (pin "119") (pinfunction "PP1/C2-/SSI3XDAT3/U6TX_119") (pintype "bidirectional+no_connect"))
    )
    (net (code "97") (name "unconnected-(U6A-PP2{slash}EPI0S29{slash}U0DTR{slash}USB0NXT-Pad103)") (class "Default")
      (node (ref "U6") (pin "103") (pinfunction "PP2/EPI0S29/U0DTR/USB0NXT_103") (pintype "bidirectional+no_connect"))
    )
    (net (code "98") (name "unconnected-(U6A-PP3{slash}EPI0S30{slash}RTCCLK{slash}U0DCD{slash}U1CTS{slash}USB0DIR-Pad104)") (class "Default")
      (node (ref "U6") (pin "104") (pinfunction "PP3/EPI0S30/RTCCLK/U0DCD/U1CTS/USB0DIR_104") (pintype "bidirectional+no_connect"))
    )
    (net (code "99") (name "unconnected-(U6A-PP4{slash}U0DSR{slash}U3RTS{slash}USB0D7-Pad105)") (class "Default")
      (node (ref "U6") (pin "105") (pinfunction "PP4/U0DSR/U3RTS/USB0D7_105") (pintype "bidirectional+no_connect"))
    )
    (net (code "100") (name "unconnected-(U6A-PP5{slash}I2C2SCL{slash}U3CTS{slash}USB0D6-Pad106)") (class "Default")
      (node (ref "U6") (pin "106") (pinfunction "PP5/I2C2SCL/U3CTS/USB0D6_106") (pintype "bidirectional+no_connect"))
    )
    (net (code "101") (name "unconnected-(U6A-PQ0{slash}EPI0S20{slash}SSI3CLK-Pad5)") (class "Default")
      (node (ref "U6") (pin "5") (pinfunction "PQ0/EPI0S20/SSI3CLK_5") (pintype "bidirectional+no_connect"))
    )
    (net (code "102") (name "unconnected-(U6A-PQ1{slash}EPI0S21{slash}SSI3FSS-Pad6)") (class "Default")
      (node (ref "U6") (pin "6") (pinfunction "PQ1/EPI0S21/SSI3FSS_6") (pintype "bidirectional+no_connect"))
    )
    (net (code "103") (name "unconnected-(U6A-PQ2{slash}EPI0S22{slash}SSI3XDAT0-Pad11)") (class "Default")
      (node (ref "U6") (pin "11") (pinfunction "PQ2/EPI0S22/SSI3XDAT0_11") (pintype "bidirectional+no_connect"))
    )
    (net (code "104") (name "unconnected-(U6A-PQ3{slash}EPI0S23{slash}SSI3XDAT1-Pad27)") (class "Default")
      (node (ref "U6") (pin "27") (pinfunction "PQ3/EPI0S23/SSI3XDAT1_27") (pintype "bidirectional+no_connect"))
    )
    (net (code "105") (name "unconnected-(U6A-PQ4{slash}DIVSCLK{slash}U1RX-Pad102)") (class "Default")
      (node (ref "U6") (pin "102") (pinfunction "PQ4/DIVSCLK/U1RX_102") (pintype "bidirectional+no_connect"))
    )
    (net (code "106") (name "unconnected-(U6B-EN0RXIN-Pad53)") (class "Default")
      (node (ref "U6") (pin "53") (pinfunction "EN0RXIN_53") (pintype "input+no_connect"))
    )
    (net (code "107") (name "unconnected-(U6B-EN0RXIP-Pad54)") (class "Default")
      (node (ref "U6") (pin "54") (pinfunction "EN0RXIP_54") (pintype "input+no_connect"))
    )
    (net (code "108") (name "unconnected-(U6B-EN0TXON-Pad56)") (class "Default")
      (node (ref "U6") (pin "56") (pinfunction "EN0TXON_56") (pintype "output+no_connect"))
    )
    (net (code "109") (name "unconnected-(U6B-EN0TXOP-Pad57)") (class "Default")
      (node (ref "U6") (pin "57") (pinfunction "EN0TXOP_57") (pintype "output+no_connect"))
    )
    (net (code "110") (name "unconnected-(U6B-XOSC1-Pad67)") (class "Default")
      (node (ref "U6") (pin "67") (pinfunction "XOSC1_67") (pintype "passive+no_connect"))
    )
    (net (code "111") (name "unconnected-(U6B-~{HIB}-Pad65)") (class "Default")
      (node (ref "U6") (pin "65") (pinfunction "~{HIB}_65") (pintype "output+no_connect"))
    )
    (net (code "112") (name "unconnected-(U7-NC-Pad3)") (class "Default")
      (node (ref "U7") (pin "3") (pinfunction "NC_3") (pintype "passive+no_connect"))
    )
  )
)
